# ADC.net
KiCad netlist of a schematic drawn in Altium Designer
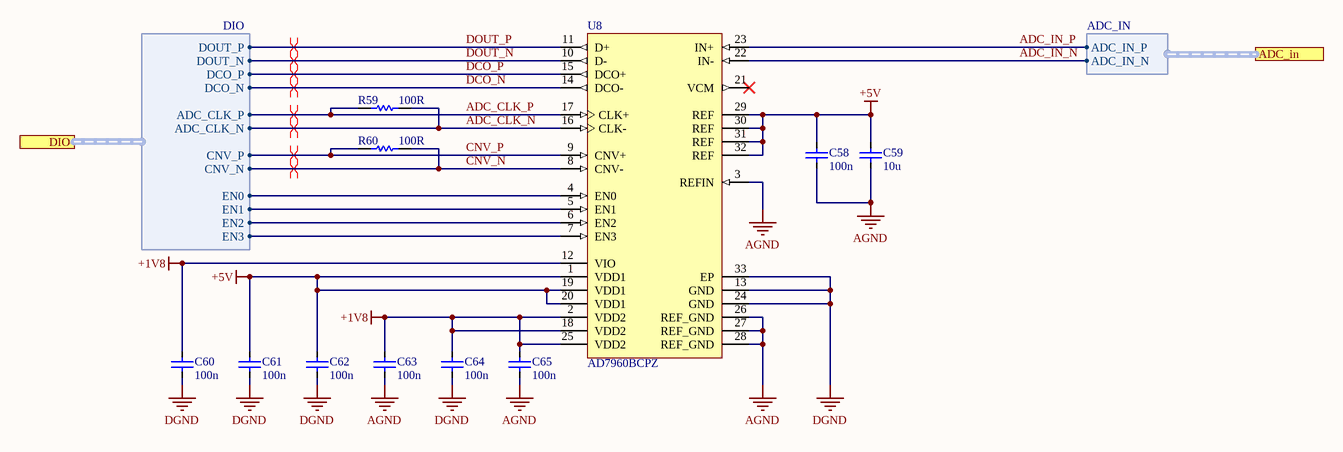
[diagram p0: ADC.SchDoc]

(export (version "E")
  (design (tool "Eeschema 10.0.6"))
  (components
    (comp (ref "C58") (value "100n") (footprint "CAP_0402") (libsource (lib "IIS-Lib_TW") (part "Cap")))
    (comp (ref "C59") (value "10u") (footprint "CAP_0603") (libsource (lib "IIS-Lib_TW") (part "Cap")))
    (comp (ref "C60") (value "100n") (footprint "CAP_0402") (libsource (lib "IIS-Lib_TW") (part "Cap")))
    (comp (ref "C61") (value "100n") (footprint "CAP_0402") (libsource (lib "IIS-Lib_TW") (part "Cap")))
    (comp (ref "C62") (value "100n") (footprint "CAP_0402") (libsource (lib "IIS-Lib_TW") (part "Cap")))
    (comp (ref "C63") (value "100n") (footprint "CAP_0402") (libsource (lib "IIS-Lib_TW") (part "Cap")))
    (comp (ref "C64") (value "100n") (footprint "CAP_0402") (libsource (lib "IIS-Lib_TW") (part "Cap")))
    (comp (ref "C65") (value "100n") (footprint "CAP_0402") (libsource (lib "IIS-Lib_TW") (part "Cap")))
    (comp (ref "R59") (value "100R") (footprint "RES_0402") (libsource (lib "IIS-Lib_TW") (part "Res")))
    (comp (ref "R60") (value "100R") (footprint "RES_0402") (libsource (lib "IIS-Lib_TW") (part "Res")))
    (comp (ref "U8")
      (value "AD7960BCPZ")
      (footprint "ADI-CP-32-7_M")
      (fields (field (name "MANUFACTURER") "Analog Devices"))
      (libsource (lib "IIS-Lib_TW") (part "AD7960"))
    )
  )
  (nets
    (net (code "3") (name "+1V8") (class "Default")
      (node (ref "C60") (pin "1") (pinfunction "1_1") (pintype "passive"))
      (node (ref "C63") (pin "1") (pinfunction "1_1") (pintype "passive"))
      (node (ref "C64") (pin "1") (pinfunction "1_1") (pintype "passive"))
      (node (ref "C65") (pin "1") (pinfunction "1_1") (pintype "passive"))
      (node (ref "U8") (pin "12") (pinfunction "VIO_12") (pintype "power_in"))
      (node (ref "U8") (pin "18") (pinfunction "VDD2_18") (pintype "power_in"))
      (node (ref "U8") (pin "2") (pinfunction "VDD2_2") (pintype "power_in"))
      (node (ref "U8") (pin "25") (pinfunction "VDD2_25") (pintype "power_in"))
    )
    (net (code "4") (name "+5V") (class "Default")
      (node (ref "C58") (pin "1") (pinfunction "1_1") (pintype "passive"))
      (node (ref "C59") (pin "1") (pinfunction "1_1") (pintype "passive"))
      (node (ref "C61") (pin "1") (pinfunction "1_1") (pintype "passive"))
      (node (ref "C62") (pin "1") (pinfunction "1_1") (pintype "passive"))
      (node (ref "U8") (pin "1") (pinfunction "VDD1_1") (pintype "power_in"))
      (node (ref "U8") (pin "19") (pinfunction "VDD1_19") (pintype "power_in"))
      (node (ref "U8") (pin "20") (pinfunction "VDD1_20") (pintype "power_in"))
      (node (ref "U8") (pin "29") (pinfunction "REF_29") (pintype "passive"))
      (node (ref "U8") (pin "30") (pinfunction "REF_30") (pintype "passive"))
      (node (ref "U8") (pin "31") (pinfunction "REF_31") (pintype "passive"))
      (node (ref "U8") (pin "32") (pinfunction "REF_32") (pintype "passive"))
    )
    (net (code "5") (name "/ADC_CLK_N") (class "Default")
      (node (ref "R59") (pin "2") (pinfunction "2_2") (pintype "passive"))
      (node (ref "U8") (pin "16") (pinfunction "CLK-_16") (pintype "input"))
    )
    (net (code "6") (name "/ADC_CLK_P") (class "Default")
      (node (ref "R59") (pin "1") (pinfunction "1_1") (pintype "passive"))
      (node (ref "U8") (pin "17") (pinfunction "CLK+_17") (pintype "input"))
    )
    (net (code "7") (name "/ADC_IN_N") (class "Default")
      (node (ref "U8") (pin "22") (pinfunction "IN-_22") (pintype "input"))
    )
    (net (code "8") (name "/ADC_IN_P") (class "Default")
      (node (ref "U8") (pin "23") (pinfunction "IN+_23") (pintype "input"))
    )
    (net (code "9") (name "/CNV_N") (class "Default")
      (node (ref "R60") (pin "2") (pinfunction "2_2") (pintype "passive"))
      (node (ref "U8") (pin "8") (pinfunction "CNV-_8") (pintype "input"))
    )
    (net (code "10") (name "/CNV_P") (class "Default")
      (node (ref "R60") (pin "1") (pinfunction "1_1") (pintype "passive"))
      (node (ref "U8") (pin "9") (pinfunction "CNV+_9") (pintype "input"))
    )
    (net (code "11") (name "/DCO_N") (class "Default")
      (node (ref "U8") (pin "14") (pinfunction "DCO-_14") (pintype "output"))
    )
    (net (code "12") (name "/DCO_P") (class "Default")
      (node (ref "U8") (pin "15") (pinfunction "DCO+_15") (pintype "output"))
    )
    (net (code "13") (name "/DOUT_N") (class "Default")
      (node (ref "U8") (pin "10") (pinfunction "D-_10") (pintype "output"))
    )
    (net (code "14") (name "/DOUT_P") (class "Default")
      (node (ref "U8") (pin "11") (pinfunction "D+_11") (pintype "output"))
    )
    (net (code "15") (name "/EN0") (class "Default")
      (node (ref "U8") (pin "4") (pinfunction "EN0_4") (pintype "input"))
    )
    (net (code "16") (name "/EN1") (class "Default")
      (node (ref "U8") (pin "5") (pinfunction "EN1_5") (pintype "input"))
    )
    (net (code "17") (name "/EN2") (class "Default")
      (node (ref "U8") (pin "6") (pinfunction "EN2_6") (pintype "input"))
    )
    (net (code "18") (name "/EN3") (class "Default")
      (node (ref "U8") (pin "7") (pinfunction "EN3_7") (pintype "input"))
    )
    (net (code "21") (name "AGND") (class "Default")
      (node (ref "C58") (pin "2") (pinfunction "2_2") (pintype "passive"))
      (node (ref "C59") (pin "2") (pinfunction "2_2") (pintype "passive"))
      (node (ref "C63") (pin "2") (pinfunction "2_2") (pintype "passive"))
      (node (ref "C65") (pin "2") (pinfunction "2_2") (pintype "passive"))
      (node (ref "U8") (pin "26") (pinfunction "REF_GND_26") (pintype "power_in"))
      (node (ref "U8") (pin "27") (pinfunction "REF_GND_27") (pintype "power_in"))
      (node (ref "U8") (pin "28") (pinfunction "REF_GND_28") (pintype "power_in"))
      (node (ref "U8") (pin "3") (pinfunction "REFIN_3") (pintype "input"))
    )
    (net (code "22") (name "DGND") (class "Default")
      (node (ref "C60") (pin "2") (pinfunction "2_2") (pintype "passive"))
      (node (ref "C61") (pin "2") (pinfunction "2_2") (pintype "passive"))
      (node (ref "C62") (pin "2") (pinfunction "2_2") (pintype "passive"))
      (node (ref "C64") (pin "2") (pinfunction "2_2") (pintype "passive"))
      (node (ref "U8") (pin "13") (pinfunction "GND_13") (pintype "power_in"))
      (node (ref "U8") (pin "24") (pinfunction "GND_24") (pintype "power_in"))
      (node (ref "U8") (pin "33") (pinfunction "EP_33") (pintype "power_in"))
    )
    (net (code "23") (name "unconnected-(U8-VCM-Pad21)") (class "Default")
      (node (ref "U8") (pin "21") (pinfunction "VCM_21") (pintype "output+no_connect"))
    )
  )
)
